# Ref_2V5_LM4132AMF.net
KiCad netlist of a schematic drawn in Altium Designer
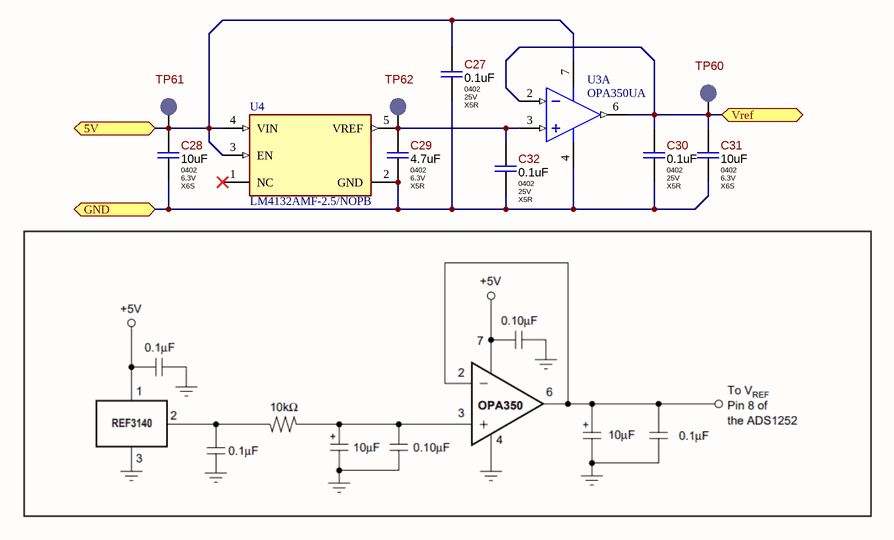
[diagram p0: Ref_2V5_LM4132AMF.SchDoc]

(export (version "E")
  (design (tool "Eeschema 10.0.6"))
  (components
    (comp (ref "C27")
      (value "0.1uF")
      (footprint "C_CERAMIC_0402_MED")
      (description "100nF 25V X5R ±10% 0402 Ceramic Capacitor RoHS")
      (fields
        (field (name "PACKAGE") "0402")
        (field (name "VOLTAGE") "25V")
        (field (name "DIELECTRIC TYPE") "X5R")
        (field (name "PART NUMBER") "CL05A104KA5NNNC")
        (field (name "MANUFACTURER") "Samsung Electro-Mechanics")
      )
      (libsource (lib "EL.XXX.T01") (part "Capacitor-NonPolar"))
    )
    (comp (ref "C28")
      (value "10uF")
      (footprint "C_CERAMIC_0402_MED")
      (description "10uF 6.3V X6S ±20% 0402 Ceramic Capacitor RoHS")
      (fields
        (field (name "PACKAGE") "0402")
        (field (name "VOLTAGE") "6.3V")
        (field (name "DIELECTRIC TYPE") "X6S")
        (field (name "PART NUMBER") "GRM155C80J106ME11D")
        (field (name "MANUFACTURER") "Murata Electronics")
      )
      (libsource (lib "EL.XXX.T01") (part "Capacitor-NonPolar"))
    )
    (comp (ref "C29")
      (value "4.7uF")
      (footprint "C_CERAMIC_0402_MED")
      (description "4.7uF 6.3V X5R ±20% 0402 Ceramic Capacitor RoHS")
      (fields
        (field (name "PACKAGE") "0402")
        (field (name "VOLTAGE") "6.3V")
        (field (name "DIELECTRIC TYPE") "X5R")
        (field (name "PART NUMBER") "GRM155R60J475ME47")
        (field (name "MANUFACTURER") "Murata Electronics")
      )
      (libsource (lib "EL.XXX.T01") (part "Capacitor-NonPolar"))
    )
    (comp (ref "C30")
      (value "0.1uF")
      (footprint "C_CERAMIC_0402_MED")
      (description "100nF 25V X5R ±10% 0402 Ceramic Capacitor RoHS")
      (fields
        (field (name "PACKAGE") "0402")
        (field (name "VOLTAGE") "25V")
        (field (name "DIELECTRIC TYPE") "X5R")
        (field (name "PART NUMBER") "CL05A104KA5NNNC")
        (field (name "MANUFACTURER") "Samsung Electro-Mechanics")
      )
      (libsource (lib "EL.XXX.T01") (part "Capacitor-NonPolar"))
    )
    (comp (ref "C31")
      (value "10uF")
      (footprint "C_CERAMIC_0402_MED")
      (description "10uF 6.3V X6S ±20% 0402 Ceramic Capacitor RoHS")
      (fields
        (field (name "PACKAGE") "0402")
        (field (name "VOLTAGE") "6.3V")
        (field (name "DIELECTRIC TYPE") "X6S")
        (field (name "PART NUMBER") "GRM155C80J106ME11D")
        (field (name "MANUFACTURER") "Murata Electronics")
      )
      (libsource (lib "EL.XXX.T01") (part "Capacitor-NonPolar"))
    )
    (comp (ref "C32")
      (value "0.1uF")
      (footprint "C_CERAMIC_0402_MED")
      (description "100nF 25V X5R ±10% 0402 Ceramic Capacitor RoHS")
      (fields
        (field (name "PACKAGE") "0402")
        (field (name "VOLTAGE") "25V")
        (field (name "DIELECTRIC TYPE") "X5R")
        (field (name "PART NUMBER") "CL05A104KA5NNNC")
        (field (name "MANUFACTURER") "Samsung Electro-Mechanics")
      )
      (libsource (lib "EL.XXX.T01") (part "Capacitor-NonPolar"))
    )
    (comp (ref "TP60")
      (value "LED_LINK")
      (footprint "TP_SMD_2mm")
      (description "Test Point SMD Pad 1.0mm/1.5mm/2mm")
      (fields (field (name "PART NUMBER") "TP-PAD-SMD"))
      (libsource (lib "EL.XXX.T01") (part "Test-Point-SMD-1"))
    )
    (comp (ref "TP61")
      (value "LED_LINK")
      (footprint "TP_SMD_2mm")
      (description "Test Point SMD Pad 1.0mm/1.5mm/2mm")
      (fields (field (name "PART NUMBER") "TP-PAD-SMD"))
      (libsource (lib "EL.XXX.T01") (part "Test-Point-SMD-1"))
    )
    (comp (ref "TP62")
      (value "LED_LINK")
      (footprint "TP_SMD_2mm")
      (description "Test Point SMD Pad 1.0mm/1.5mm/2mm")
      (fields (field (name "PART NUMBER") "TP-PAD-SMD"))
      (libsource (lib "EL.XXX.T01") (part "Test-Point-SMD-1"))
    )
    (comp (ref "U3")
      (value "OPA350UA")
      (footprint "D0008A_M")
      (fields (field (name "MANUFACTURER") "Texas Instruments"))
      (libsource (lib "EL.XXX.T01") (part "TI-OPA-8_1"))
    )
    (comp (ref "U4")
      (value "LM4132AMF-2.5/NOPB")
      (footprint "FP-DBV0005A-IPC_C")
      (description "IC VREF SERIES 0.05% SOT23-5")
      (fields (field (name "TOLERANCE") "0.05%"))
      (libsource (lib "EL.XXX.T01") (part "83a8c20666b8818ecf60699c622df6d"))
    )
  )
  (nets
    (net (code "1") (name "/5V") (class "Default")
      (node (ref "C27") (pin "1") (pinfunction "1_1") (pintype "passive"))
      (node (ref "C28") (pin "1") (pinfunction "1_1") (pintype "passive"))
      (node (ref "TP61") (pin "1") (pintype "passive"))
      (node (ref "U3") (pin "7") (pinfunction "V+_7") (pintype "power_in"))
      (node (ref "U4") (pin "3") (pinfunction "EN_3") (pintype "input"))
      (node (ref "U4") (pin "4") (pinfunction "VIN_4") (pintype "input"))
    )
    (net (code "2") (name "/GND") (class "Default")
      (node (ref "C27") (pin "2") (pinfunction "2_2") (pintype "passive"))
      (node (ref "C28") (pin "2") (pinfunction "2_2") (pintype "passive"))
      (node (ref "C29") (pin "2") (pinfunction "2_2") (pintype "passive"))
      (node (ref "C30") (pin "2") (pinfunction "2_2") (pintype "passive"))
      (node (ref "C31") (pin "2") (pinfunction "2_2") (pintype "passive"))
      (node (ref "C32") (pin "2") (pinfunction "2_2") (pintype "passive"))
      (node (ref "U3") (pin "4") (pinfunction "V-_4") (pintype "power_in"))
      (node (ref "U4") (pin "2") (pinfunction "GND_2") (pintype "power_in"))
    )
    (net (code "3") (name "/Vref") (class "Default")
      (node (ref "C30") (pin "1") (pinfunction "1_1") (pintype "passive"))
      (node (ref "C31") (pin "1") (pinfunction "1_1") (pintype "passive"))
      (node (ref "TP60") (pin "1") (pintype "passive"))
      (node (ref "U3") (pin "2") (pinfunction "IN-_2") (pintype "input"))
      (node (ref "U3") (pin "6") (pinfunction "OUT_6") (pintype "output"))
    )
    (net (code "4") (name "Net-(U3A-IN+)") (class "Default")
      (node (ref "C29") (pin "1") (pinfunction "1_1") (pintype "passive"))
      (node (ref "C32") (pin "1") (pinfunction "1_1") (pintype "passive"))
      (node (ref "TP62") (pin "1") (pintype "passive"))
      (node (ref "U3") (pin "3") (pinfunction "IN+_3") (pintype "input"))
      (node (ref "U4") (pin "5") (pinfunction "VREF_5") (pintype "output"))
    )
    (net (code "5") (name "unconnected-(U4-NC-Pad1)") (class "Default")
      (node (ref "U4") (pin "1") (pinfunction "NC_1") (pintype "passive+no_connect"))
    )
  )
)
